# Grove_Shield.net
KiCad netlist of a schematic drawn in EAGLE
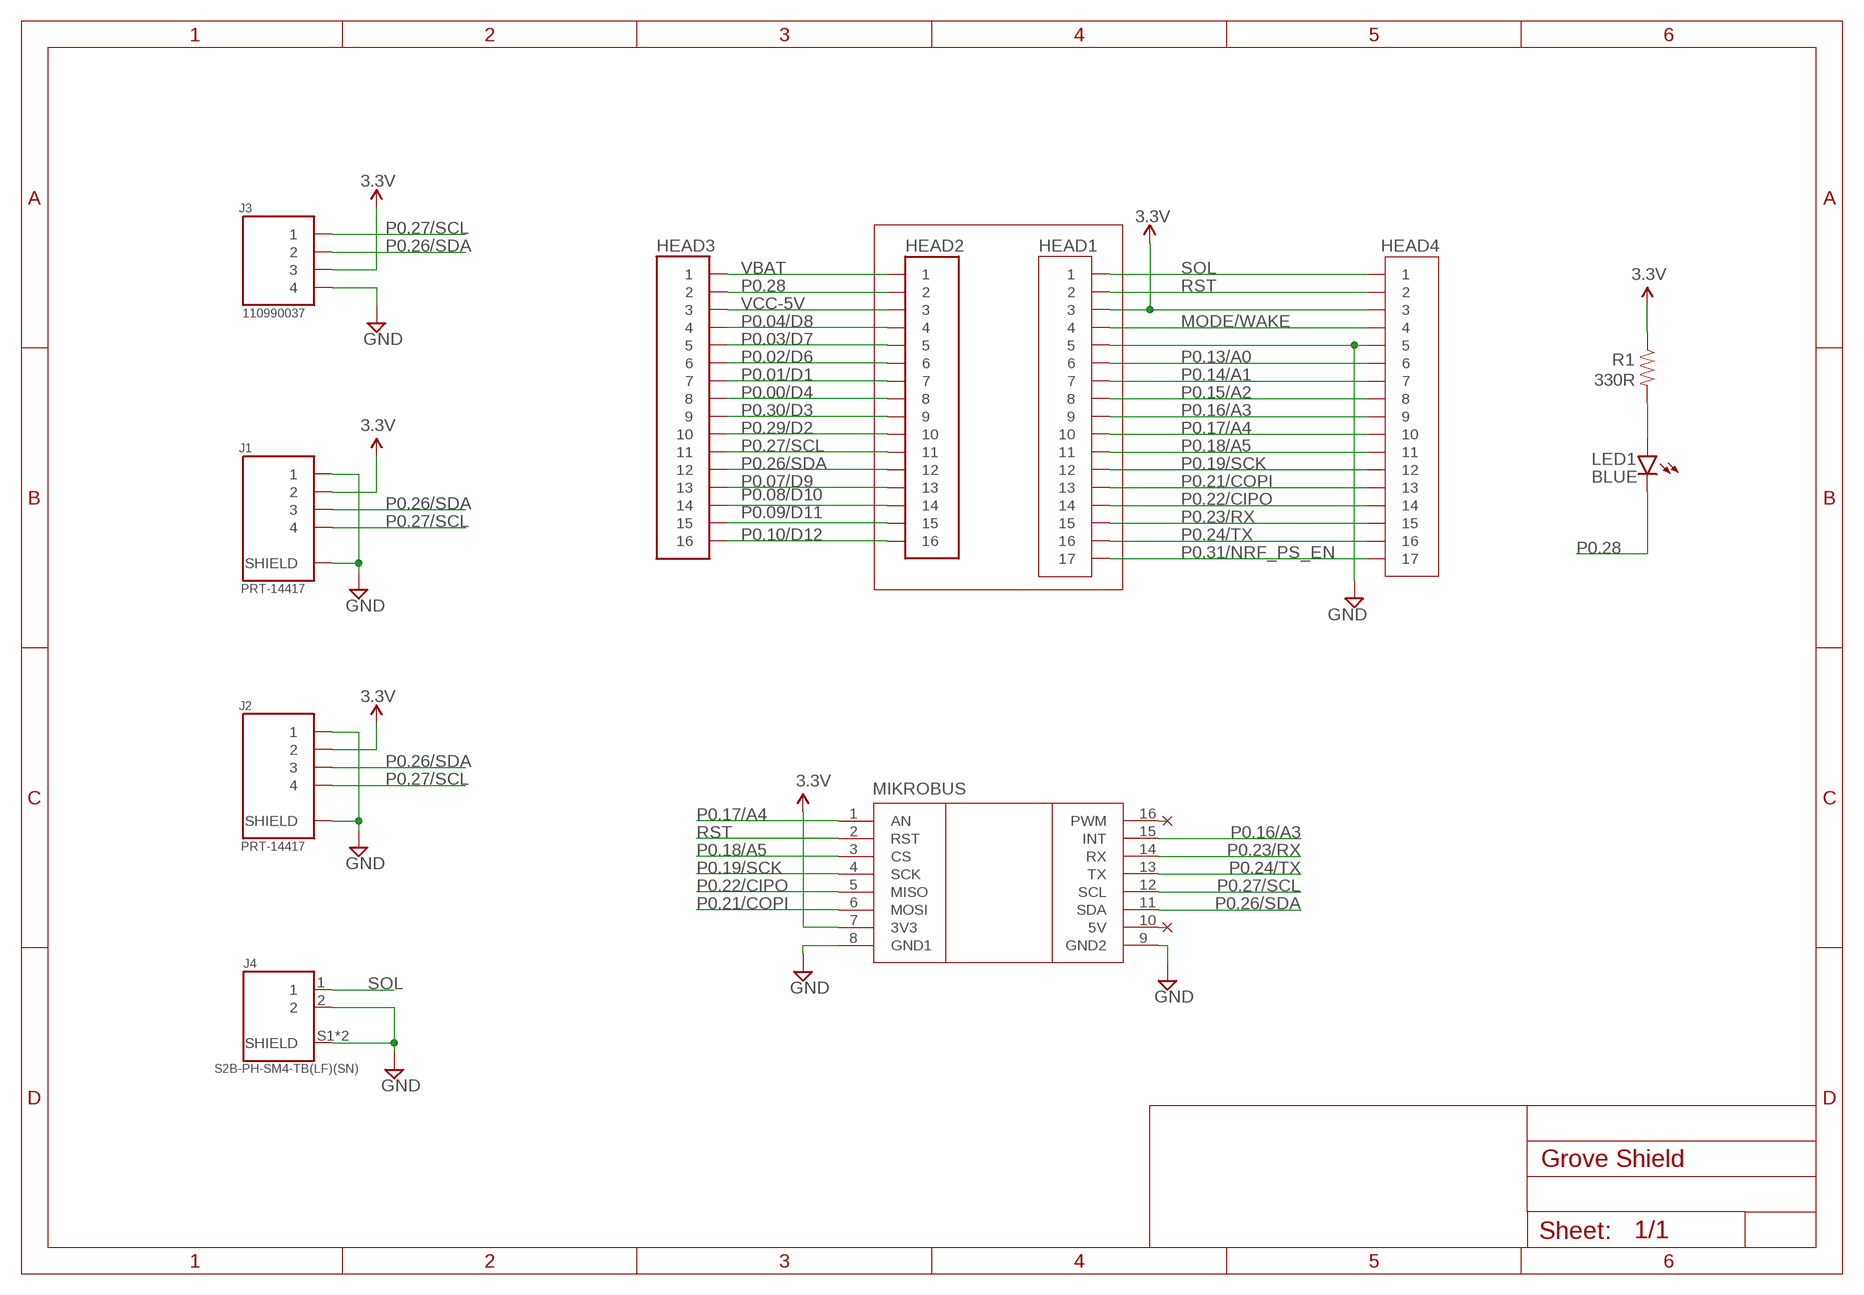
[diagram p0: schematic, sheet 1]

(export (version "E")
  (design (tool "Eeschema 10.0.6"))
  (components
    (comp (ref "HEAD1")
      (value "HEADER_16P")
      (footprint "eagle-import:HEADER_16P2.54")
      (libsource (lib "eagle-import") (part "HEADER_16P"))
    )
    (comp (ref "HEAD2")
      (value "SIP-12")
      (footprint "eagle-import:SIP-12")
      (libsource (lib "eagle-import") (part "SIP-12"))
    )
    (comp (ref "HEAD3")
      (value "SIP-12")
      (footprint "eagle-import:SIP-12")
      (libsource (lib "eagle-import") (part "SIP-12"))
    )
    (comp (ref "HEAD4")
      (value "HEADER_16P")
      (footprint "eagle-import:HEADER_16P2.54")
      (libsource (lib "eagle-import") (part "HEADER_16P"))
    )
    (comp (ref "J1")
      (value "PRT-14417")
      (footprint "eagle-import:JST_SM04B-SRSS-TB(LF)(SN)")
      (fields (field (name "MF") "JST Sales") (field (name "MP") "SM04B-SRSS-TB(LF)(SN)"))
      (libsource (lib "eagle-import") (part "SM04B-SRSS-TB(LF)(SN)"))
    )
    (comp (ref "J2")
      (value "PRT-14417")
      (footprint "eagle-import:JST_SM04B-SRSS-TB(LF)(SN)")
      (fields (field (name "MF") "JST Sales") (field (name "MP") "SM04B-SRSS-TB(LF)(SN)"))
      (libsource (lib "eagle-import") (part "SM04B-SRSS-TB(LF)(SN)"))
    )
    (comp (ref "J3")
      (value "110990037")
      (footprint "eagle-import:HW4-2.0-90D")
      (libsource (lib "eagle-import") (part "11099003790D"))
    )
    (comp (ref "J4")
      (value "S2B-PH-SM4-TB(LF)(SN)")
      (footprint "eagle-import:JST_S2B-PH-SM4-TB(LF)(SN)")
      (fields (field (name "DIGI-KEY_PART_NUMBER") "455-1749-1-ND") (field (name "MF") "JST Sales"))
      (libsource (lib "eagle-import") (part "S2B-PH-SM4-TB(LF)(SN)"))
    )
    (comp (ref "J11")
      (value "MIKROBUS")
      (footprint "eagle-import:MIKROBUS")
      (libsource (lib "eagle-import") (part "MIKROBUS"))
    )
    (comp (ref "LED1")
      (value "BLUE")
      (footprint "eagle-import:LED-0603")
      (fields
        (field (name "MANUFACTURER") "Osram")
        (field (name "MANUFACTURER_PART_NUMBER") "LO L29K-H2L1-24-Z")
      )
      (libsource (lib "eagle-import") (part "LOL29K-H2L1-24-Z"))
    )
    (comp (ref "R1")
      (value "330R")
      (footprint "eagle-import:R-0603")
      (libsource (lib "eagle-import") (part "R-0603"))
    )
  )
  (nets
    (net (code "1") (name "/MODE{slash}WAKE") (class "Default")
      (node (ref "HEAD1") (pin "4") (pinfunction "4_4") (pintype "passive"))
      (node (ref "HEAD4") (pin "4") (pinfunction "4_4") (pintype "passive"))
    )
    (net (code "2") (name "/P0.00{slash}D4") (class "Default")
      (node (ref "HEAD2") (pin "8") (pinfunction "8_8") (pintype "passive"))
      (node (ref "HEAD3") (pin "8") (pinfunction "8_8") (pintype "passive"))
    )
    (net (code "3") (name "/P0.01{slash}D1") (class "Default")
      (node (ref "HEAD2") (pin "7") (pinfunction "7_7") (pintype "passive"))
      (node (ref "HEAD3") (pin "7") (pinfunction "7_7") (pintype "passive"))
    )
    (net (code "4") (name "/P0.02{slash}D6") (class "Default")
      (node (ref "HEAD2") (pin "6") (pinfunction "6_6") (pintype "passive"))
      (node (ref "HEAD3") (pin "6") (pinfunction "6_6") (pintype "passive"))
    )
    (net (code "5") (name "/P0.03{slash}D7") (class "Default")
      (node (ref "HEAD2") (pin "5") (pinfunction "5_5") (pintype "passive"))
      (node (ref "HEAD3") (pin "5") (pinfunction "5_5") (pintype "passive"))
    )
    (net (code "6") (name "/P0.04{slash}D8") (class "Default")
      (node (ref "HEAD2") (pin "4") (pinfunction "4_4") (pintype "passive"))
      (node (ref "HEAD3") (pin "4") (pinfunction "4_4") (pintype "passive"))
    )
    (net (code "7") (name "/P0.07{slash}D9") (class "Default")
      (node (ref "HEAD2") (pin "13") (pinfunction "13_13") (pintype "passive"))
      (node (ref "HEAD3") (pin "13") (pinfunction "13_13") (pintype "passive"))
    )
    (net (code "8") (name "/P0.08{slash}D10") (class "Default")
      (node (ref "HEAD2") (pin "14") (pinfunction "14_14") (pintype "passive"))
      (node (ref "HEAD3") (pin "14") (pinfunction "14_14") (pintype "passive"))
    )
    (net (code "9") (name "/P0.09{slash}D11") (class "Default")
      (node (ref "HEAD2") (pin "15") (pinfunction "15_15") (pintype "passive"))
      (node (ref "HEAD3") (pin "15") (pinfunction "15_15") (pintype "passive"))
    )
    (net (code "10") (name "/P0.10{slash}D12") (class "Default")
      (node (ref "HEAD2") (pin "16") (pinfunction "16_16") (pintype "passive"))
      (node (ref "HEAD3") (pin "16") (pinfunction "16_16") (pintype "passive"))
    )
    (net (code "11") (name "/P0.13{slash}A0") (class "Default")
      (node (ref "HEAD1") (pin "6") (pinfunction "6_6") (pintype "passive"))
      (node (ref "HEAD4") (pin "6") (pinfunction "6_6") (pintype "passive"))
    )
    (net (code "12") (name "/P0.14{slash}A1") (class "Default")
      (node (ref "HEAD1") (pin "7") (pinfunction "7_7") (pintype "passive"))
      (node (ref "HEAD4") (pin "7") (pinfunction "7_7") (pintype "passive"))
    )
    (net (code "13") (name "/P0.15{slash}A2") (class "Default")
      (node (ref "HEAD1") (pin "8") (pinfunction "8_8") (pintype "passive"))
      (node (ref "HEAD4") (pin "8") (pinfunction "8_8") (pintype "passive"))
    )
    (net (code "14") (name "/P0.16{slash}A3") (class "Default")
      (node (ref "HEAD1") (pin "9") (pinfunction "9_9") (pintype "passive"))
      (node (ref "HEAD4") (pin "9") (pinfunction "9_9") (pintype "passive"))
      (node (ref "J11") (pin "15") (pinfunction "INT_15") (pintype "passive"))
    )
    (net (code "15") (name "/P0.17{slash}A4") (class "Default")
      (node (ref "HEAD1") (pin "10") (pinfunction "10_10") (pintype "passive"))
      (node (ref "HEAD4") (pin "10") (pinfunction "10_10") (pintype "passive"))
      (node (ref "J11") (pin "1") (pinfunction "AN_1") (pintype "passive"))
    )
    (net (code "16") (name "/P0.18{slash}A5") (class "Default")
      (node (ref "HEAD1") (pin "11") (pinfunction "11_11") (pintype "passive"))
      (node (ref "HEAD4") (pin "11") (pinfunction "11_11") (pintype "passive"))
      (node (ref "J11") (pin "3") (pinfunction "CS_3") (pintype "passive"))
    )
    (net (code "17") (name "/P0.19{slash}SCK") (class "Default")
      (node (ref "HEAD1") (pin "12") (pinfunction "12_12") (pintype "passive"))
      (node (ref "HEAD4") (pin "12") (pinfunction "12_12") (pintype "passive"))
      (node (ref "J11") (pin "4") (pinfunction "SCK_4") (pintype "passive"))
    )
    (net (code "18") (name "/P0.21{slash}COPI") (class "Default")
      (node (ref "HEAD1") (pin "13") (pinfunction "13_13") (pintype "passive"))
      (node (ref "HEAD4") (pin "13") (pinfunction "13_13") (pintype "passive"))
      (node (ref "J11") (pin "6") (pinfunction "MOSI_6") (pintype "passive"))
    )
    (net (code "19") (name "/P0.22{slash}CIPO") (class "Default")
      (node (ref "HEAD1") (pin "14") (pinfunction "14_14") (pintype "passive"))
      (node (ref "HEAD4") (pin "14") (pinfunction "14_14") (pintype "passive"))
      (node (ref "J11") (pin "5") (pinfunction "MISO_5") (pintype "passive"))
    )
    (net (code "20") (name "/P0.23{slash}RX") (class "Default")
      (node (ref "HEAD1") (pin "15") (pinfunction "15_15") (pintype "passive"))
      (node (ref "HEAD4") (pin "15") (pinfunction "15_15") (pintype "passive"))
      (node (ref "J11") (pin "14") (pinfunction "RX_14") (pintype "passive"))
    )
    (net (code "21") (name "/P0.24{slash}TX") (class "Default")
      (node (ref "HEAD1") (pin "16") (pinfunction "16_16") (pintype "passive"))
      (node (ref "HEAD4") (pin "16") (pinfunction "16_16") (pintype "passive"))
      (node (ref "J11") (pin "13") (pinfunction "TX_13") (pintype "passive"))
    )
    (net (code "22") (name "/P0.26{slash}SDA") (class "Default")
      (node (ref "HEAD2") (pin "12") (pinfunction "12_12") (pintype "passive"))
      (node (ref "HEAD3") (pin "12") (pinfunction "12_12") (pintype "passive"))
      (node (ref "J1") (pin "3") (pinfunction "3_3") (pintype "passive"))
      (node (ref "J11") (pin "11") (pinfunction "SDA_11") (pintype "passive"))
      (node (ref "J2") (pin "3") (pinfunction "3_3") (pintype "passive"))
      (node (ref "J3") (pin "2") (pinfunction "2_2") (pintype "passive"))
    )
    (net (code "23") (name "/P0.27{slash}SCL") (class "Default")
      (node (ref "HEAD2") (pin "11") (pinfunction "11_11") (pintype "passive"))
      (node (ref "HEAD3") (pin "11") (pinfunction "11_11") (pintype "passive"))
      (node (ref "J1") (pin "4") (pinfunction "4_4") (pintype "passive"))
      (node (ref "J11") (pin "12") (pinfunction "SCL_12") (pintype "passive"))
      (node (ref "J2") (pin "4") (pinfunction "4_4") (pintype "passive"))
      (node (ref "J3") (pin "1") (pinfunction "1_1") (pintype "passive"))
    )
    (net (code "24") (name "/P0.28") (class "Default")
      (node (ref "HEAD2") (pin "2") (pinfunction "2_2") (pintype "passive"))
      (node (ref "HEAD3") (pin "2") (pinfunction "2_2") (pintype "passive"))
      (node (ref "LED1") (pin "K") (pinfunction "C_K") (pintype "passive"))
    )
    (net (code "25") (name "/P0.29{slash}D2") (class "Default")
      (node (ref "HEAD2") (pin "10") (pinfunction "10_10") (pintype "passive"))
      (node (ref "HEAD3") (pin "10") (pinfunction "10_10") (pintype "passive"))
    )
    (net (code "26") (name "/P0.30{slash}D3") (class "Default")
      (node (ref "HEAD2") (pin "9") (pinfunction "9_9") (pintype "passive"))
      (node (ref "HEAD3") (pin "9") (pinfunction "9_9") (pintype "passive"))
    )
    (net (code "27") (name "/P0.31{slash}NRF_PS_EN") (class "Default")
      (node (ref "HEAD1") (pin "17") (pinfunction "17_17") (pintype "passive"))
      (node (ref "HEAD4") (pin "17") (pinfunction "17_17") (pintype "passive"))
    )
    (net (code "28") (name "/RST") (class "Default")
      (node (ref "HEAD1") (pin "2") (pinfunction "2_2") (pintype "passive"))
      (node (ref "HEAD4") (pin "2") (pinfunction "2_2") (pintype "passive"))
      (node (ref "J11") (pin "2") (pinfunction "RST_2") (pintype "passive"))
    )
    (net (code "29") (name "/SOL") (class "Default")
      (node (ref "HEAD1") (pin "1") (pinfunction "1_1") (pintype "passive"))
      (node (ref "HEAD4") (pin "1") (pinfunction "1_1") (pintype "passive"))
      (node (ref "J4") (pin "1") (pinfunction "1_1") (pintype "passive"))
    )
    (net (code "30") (name "/VBAT") (class "Default")
      (node (ref "HEAD2") (pin "1") (pinfunction "1_1") (pintype "passive"))
      (node (ref "HEAD3") (pin "1") (pinfunction "1_1") (pintype "passive"))
    )
    (net (code "31") (name "/VCC-5V") (class "Default")
      (node (ref "HEAD2") (pin "3") (pinfunction "3_3") (pintype "passive"))
      (node (ref "HEAD3") (pin "3") (pinfunction "3_3") (pintype "passive"))
    )
    (net (code "32") (name "3.3V") (class "Default")
      (node (ref "HEAD1") (pin "3") (pinfunction "3_3") (pintype "passive"))
      (node (ref "HEAD4") (pin "3") (pinfunction "3_3") (pintype "passive"))
      (node (ref "J1") (pin "2") (pinfunction "2_2") (pintype "passive"))
      (node (ref "J11") (pin "7") (pinfunction "3V3_7") (pintype "passive"))
      (node (ref "J2") (pin "2") (pinfunction "2_2") (pintype "passive"))
      (node (ref "J3") (pin "3") (pinfunction "3_3") (pintype "passive"))
      (node (ref "R1") (pin "1") (pinfunction "1_1") (pintype "passive"))
    )
    (net (code "33") (name "GND") (class "Default")
      (node (ref "HEAD1") (pin "5") (pinfunction "5_5") (pintype "passive"))
      (node (ref "HEAD4") (pin "5") (pinfunction "5_5") (pintype "passive"))
      (node (ref "J1") (pin "1") (pinfunction "1_1") (pintype "passive"))
      (node (ref "J1") (pin "S1") (pinfunction "SHIELD_S1") (pintype "passive"))
      (node (ref "J1") (pin "S2") (pinfunction "SHIELD_S2") (pintype "passive"))
      (node (ref "J11") (pin "8") (pinfunction "GND1_8") (pintype "passive"))
      (node (ref "J11") (pin "9") (pinfunction "GND2_9") (pintype "passive"))
      (node (ref "J2") (pin "1") (pinfunction "1_1") (pintype "passive"))
      (node (ref "J2") (pin "S1") (pinfunction "SHIELD_S1") (pintype "passive"))
      (node (ref "J2") (pin "S2") (pinfunction "SHIELD_S2") (pintype "passive"))
      (node (ref "J3") (pin "4") (pinfunction "4_4") (pintype "passive"))
      (node (ref "J4") (pin "2") (pinfunction "2_2") (pintype "passive"))
      (node (ref "J4") (pin "S1") (pinfunction "SHIELD_S1") (pintype "passive"))
      (node (ref "J4") (pin "S2") (pinfunction "SHIELD_S2") (pintype "passive"))
    )
    (net (code "34") (name "Net-(LED1-PadA)") (class "Default")
      (node (ref "LED1") (pin "A") (pinfunction "A_A") (pintype "passive"))
      (node (ref "R1") (pin "2") (pinfunction "2_2") (pintype "passive"))
    )
    (net (code "35") (name "unconnected-(J11-5V-Pad10)") (class "Default")
      (node (ref "J11") (pin "10") (pinfunction "5V_10") (pintype "passive"))
    )
    (net (code "36") (name "unconnected-(J11-PWM-Pad16)") (class "Default")
      (node (ref "J11") (pin "16") (pinfunction "PWM_16") (pintype "passive"))
    )
  )
)
